# psvemmc-v10.net
KiCad netlist of a schematic drawn in EAGLE
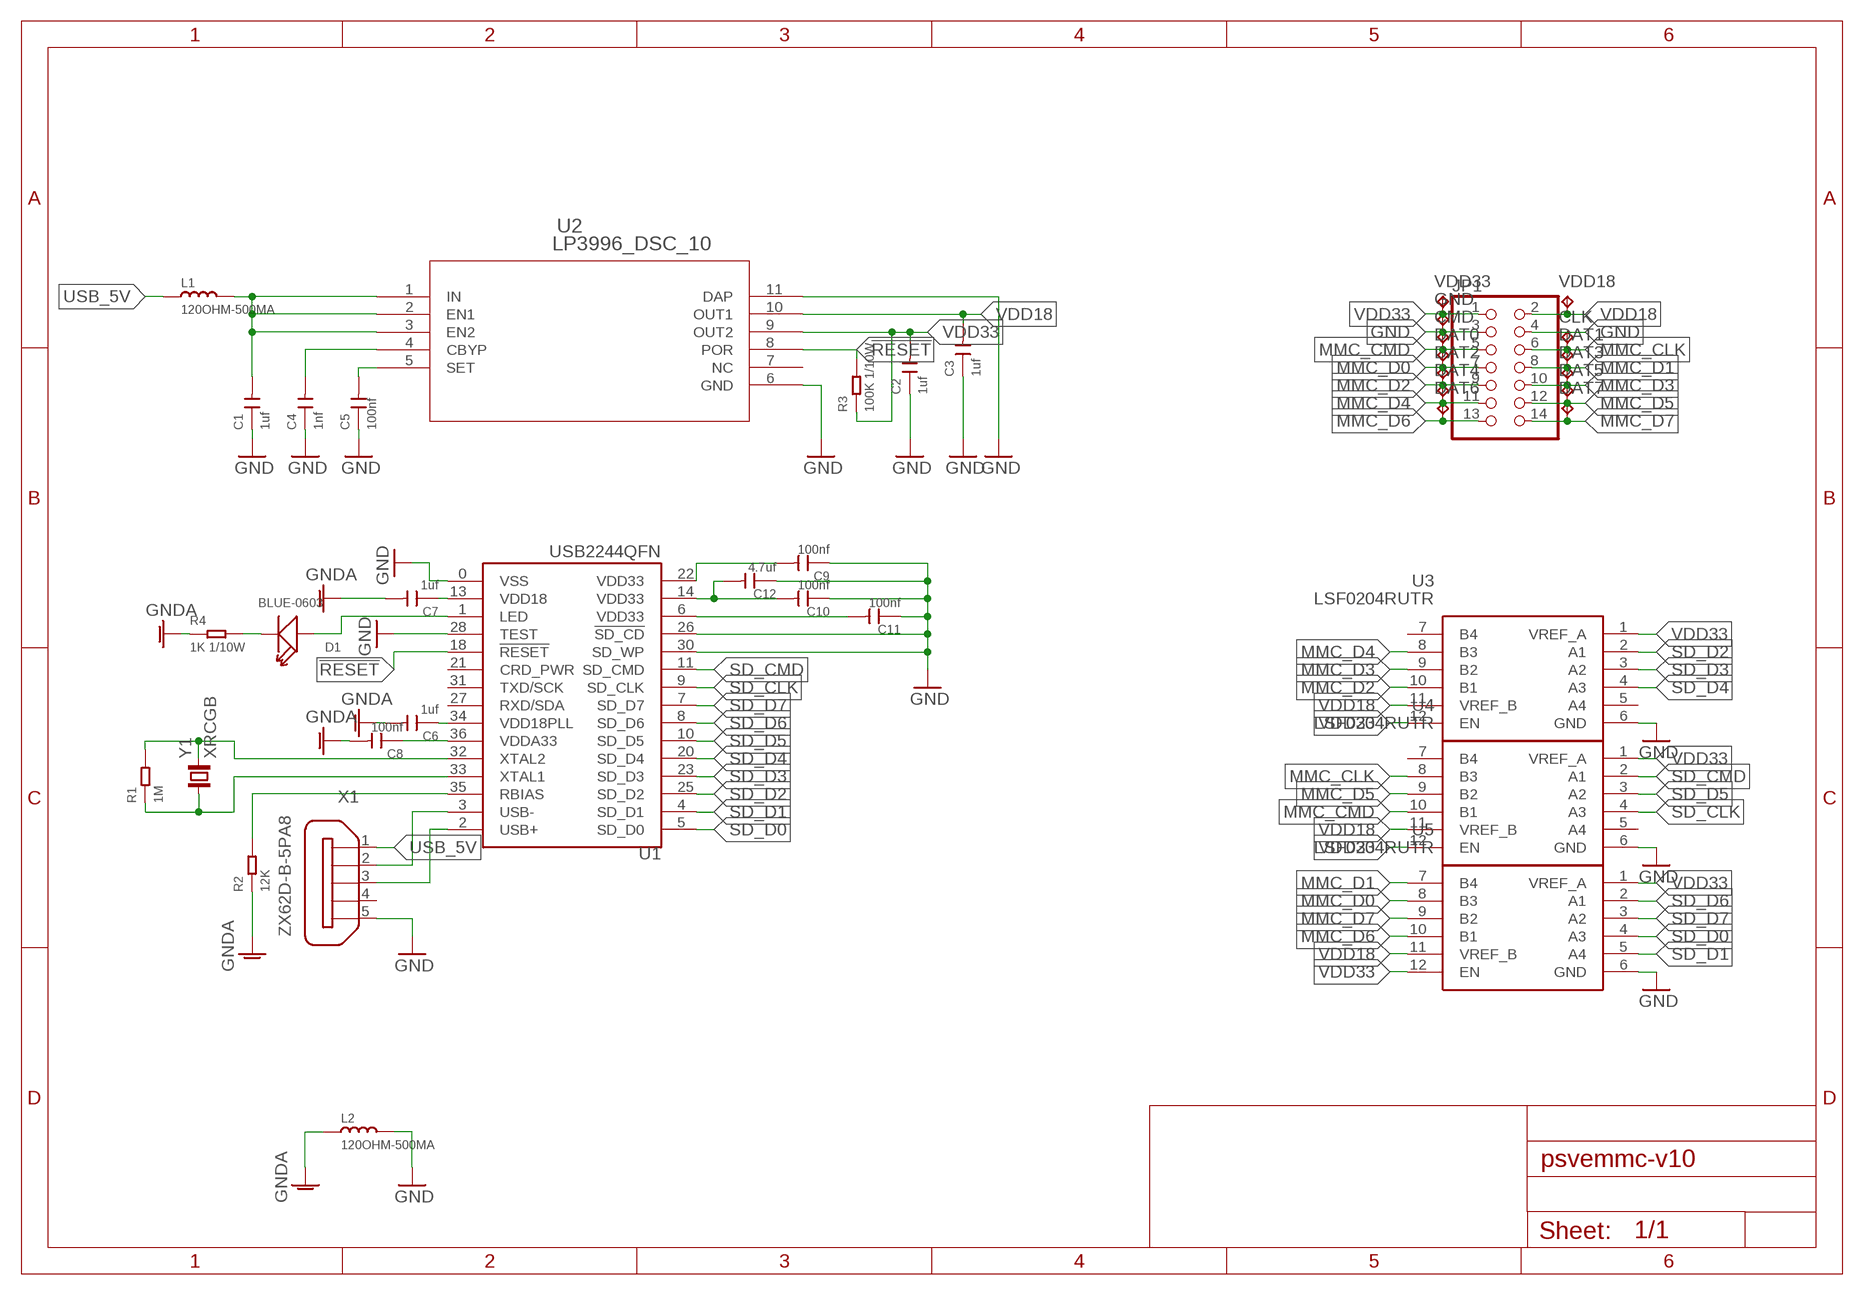
[diagram p0: schematic, sheet 1]

(export (version "E")
  (design (tool "Eeschema 10.0.6"))
  (components
    (comp (ref "C1")
      (value "1uf")
      (footprint "eagle-import:C0603")
      (fields (field (name "MPN") "CC0603KRX7R8BB105"))
      (libsource (lib "eagle-import") (part "CERAMIC-1UF-25V-10%-X7R(0603)"))
    )
    (comp (ref "C2")
      (value "1uf")
      (footprint "eagle-import:C0603")
      (fields (field (name "MPN") "CC0603KRX7R8BB105"))
      (libsource (lib "eagle-import") (part "CERAMIC-1UF-25V-10%-X7R(0603)"))
    )
    (comp (ref "C3")
      (value "1uf")
      (footprint "eagle-import:C0603")
      (fields (field (name "MPN") "CC0603KRX7R8BB105"))
      (libsource (lib "eagle-import") (part "CERAMIC-1UF-25V-10%-X7R(0603)"))
    )
    (comp (ref "C4")
      (value "1nf")
      (footprint "eagle-import:C0603")
      (fields (field (name "MPN") "GRM1885C1H102JA01D"))
      (libsource (lib "eagle-import") (part "CERAMIC-1NF-50V-5%-C0G(0603)"))
    )
    (comp (ref "C5")
      (value "100nf")
      (footprint "eagle-import:C0603")
      (fields (field (name "MPN") "CC0603KRX7R9BB104"))
      (libsource (lib "eagle-import") (part "CERAMIC-100NF-50V-10%-X7R(0603)"))
    )
    (comp (ref "C6")
      (value "1uf")
      (footprint "eagle-import:C0603")
      (fields (field (name "MPN") "CC0603KRX7R8BB105"))
      (libsource (lib "eagle-import") (part "CERAMIC-1UF-25V-10%-X7R(0603)"))
    )
    (comp (ref "C7")
      (value "1uf")
      (footprint "eagle-import:C0603")
      (fields (field (name "MPN") "CC0603KRX7R8BB105"))
      (libsource (lib "eagle-import") (part "CERAMIC-1UF-25V-10%-X7R(0603)"))
    )
    (comp (ref "C8")
      (value "100nf")
      (footprint "eagle-import:C0603")
      (fields (field (name "MPN") "CC0603KRX7R9BB104"))
      (libsource (lib "eagle-import") (part "CERAMIC-100NF-50V-10%-X7R(0603)"))
    )
    (comp (ref "C9")
      (value "100nf")
      (footprint "eagle-import:C0603")
      (fields (field (name "MPN") "CC0603KRX7R9BB104"))
      (libsource (lib "eagle-import") (part "CERAMIC-100NF-50V-10%-X7R(0603)"))
    )
    (comp (ref "C10")
      (value "100nf")
      (footprint "eagle-import:C0603")
      (fields (field (name "MPN") "CC0603KRX7R9BB104"))
      (libsource (lib "eagle-import") (part "CERAMIC-100NF-50V-10%-X7R(0603)"))
    )
    (comp (ref "C11")
      (value "100nf")
      (footprint "eagle-import:C0603")
      (fields (field (name "MPN") "CC0603KRX7R9BB104"))
      (libsource (lib "eagle-import") (part "CERAMIC-100NF-50V-10%-X7R(0603)"))
    )
    (comp (ref "C12")
      (value "4.7uf")
      (footprint "eagle-import:C0603")
      (fields (field (name "MPN") "CC0603KRX5R6BB475"))
      (libsource (lib "eagle-import") (part "CERAMIC-4.7UF-10V-10%-X5R(0603)"))
    )
    (comp (ref "CLK")
      (value "TPTP20SQ")
      (footprint "eagle-import:TP20SQ")
      (libsource (lib "eagle-import") (part "TPTP20SQ"))
    )
    (comp (ref "CMD")
      (value "TPTP20SQ")
      (footprint "eagle-import:TP20SQ")
      (libsource (lib "eagle-import") (part "TPTP20SQ"))
    )
    (comp (ref "D1")
      (value "BLUE-0603")
      (footprint "eagle-import:LED-0603")
      (fields (field (name "MPN") "19-217-BHC-ZL1M2RY-3T"))
      (libsource (lib "eagle-import") (part "SMD-LED-CLEAR-BLUE(0603)"))
    )
    (comp (ref "DAT0")
      (value "TPTP20SQ")
      (footprint "eagle-import:TP20SQ")
      (libsource (lib "eagle-import") (part "TPTP20SQ"))
    )
    (comp (ref "DAT1")
      (value "TPTP20SQ")
      (footprint "eagle-import:TP20SQ")
      (libsource (lib "eagle-import") (part "TPTP20SQ"))
    )
    (comp (ref "DAT2")
      (value "TPTP20SQ")
      (footprint "eagle-import:TP20SQ")
      (libsource (lib "eagle-import") (part "TPTP20SQ"))
    )
    (comp (ref "DAT3")
      (value "TPTP20SQ")
      (footprint "eagle-import:TP20SQ")
      (libsource (lib "eagle-import") (part "TPTP20SQ"))
    )
    (comp (ref "DAT4")
      (value "TPTP20SQ")
      (footprint "eagle-import:TP20SQ")
      (libsource (lib "eagle-import") (part "TPTP20SQ"))
    )
    (comp (ref "DAT5")
      (value "TPTP20SQ")
      (footprint "eagle-import:TP20SQ")
      (libsource (lib "eagle-import") (part "TPTP20SQ"))
    )
    (comp (ref "DAT6")
      (value "TPTP20SQ")
      (footprint "eagle-import:TP20SQ")
      (libsource (lib "eagle-import") (part "TPTP20SQ"))
    )
    (comp (ref "DAT7")
      (value "TPTP20SQ")
      (footprint "eagle-import:TP20SQ")
      (libsource (lib "eagle-import") (part "TPTP20SQ"))
    )
    (comp (ref "GND")
      (value "TPTP20SQ")
      (footprint "eagle-import:TP20SQ")
      (libsource (lib "eagle-import") (part "TPTP20SQ"))
    )
    (comp (ref "JP1")
      (value "PINHD-2X7")
      (footprint "eagle-import:2X07")
      (libsource (lib "eagle-import") (part "PINHD-2X7"))
    )
    (comp (ref "L1")
      (value "120OHM-500MA")
      (footprint "eagle-import:L0603")
      (fields (field (name "MPN") "BLM18AG121SN1D"))
      (libsource (lib "eagle-import") (part "SMD-FERRITE-CHIP-120-OHM-500MA(0603)"))
    )
    (comp (ref "L2")
      (value "120OHM-500MA")
      (footprint "eagle-import:L0603")
      (fields (field (name "MPN") "BLM18AG121SN1D"))
      (libsource (lib "eagle-import") (part "SMD-FERRITE-CHIP-120-OHM-500MA(0603)"))
    )
    (comp (ref "R1")
      (value "1M")
      (footprint "eagle-import:R0603")
      (fields (field (name "MPN") "RC0603FR-071ML"))
      (libsource (lib "eagle-import") (part "SMD-RES-1M-1%-1/10W(0603)"))
    )
    (comp (ref "R2")
      (value "12K")
      (footprint "eagle-import:R0603")
      (fields (field (name "MPN") "RC0603FR-0712KL"))
      (libsource (lib "eagle-import") (part "SMD-RES-12K-1%-1/10W(0603)"))
    )
    (comp (ref "R3")
      (value "100K 1/10W")
      (footprint "eagle-import:R0603")
      (fields (field (name "MPN") "RC0603JR-07100KL"))
      (libsource (lib "eagle-import") (part "SMD-RES-100K-5%-1/10W(0603)"))
    )
    (comp (ref "R4")
      (value "1K 1/10W")
      (footprint "eagle-import:R0603")
      (fields (field (name "MPN") "RC0603JR-071KL"))
      (libsource (lib "eagle-import") (part "SMD-RES-1K-5%-1/10W(0603)"))
    )
    (comp (ref "U1")
      (value "USB2244QFN")
      (footprint "eagle-import:QFN36")
      (libsource (lib "eagle-import") (part "USB2244QFN"))
    )
    (comp (ref "U2")
      (value "LP3996_DSC_10")
      (footprint "eagle-import:SDA10A")
      (fields (field (name "PARTNUMBER") "LP3996SD0833"))
      (libsource (lib "eagle-import") (part "LP3996_DSC_10"))
    )
    (comp (ref "U3")
      (value "LSF0204RUTR")
      (footprint "eagle-import:RUT(R-PUQFN-N12)")
      (libsource (lib "eagle-import") (part "LSF0204RUTR"))
    )
    (comp (ref "U4")
      (value "LSF0204RUTR")
      (footprint "eagle-import:RUT(R-PUQFN-N12)")
      (libsource (lib "eagle-import") (part "LSF0204RUTR"))
    )
    (comp (ref "U5")
      (value "LSF0204RUTR")
      (footprint "eagle-import:RUT(R-PUQFN-N12)")
      (libsource (lib "eagle-import") (part "LSF0204RUTR"))
    )
    (comp (ref "VDD18")
      (value "TPTP20SQ")
      (footprint "eagle-import:TP20SQ")
      (libsource (lib "eagle-import") (part "TPTP20SQ"))
    )
    (comp (ref "VDD33")
      (value "TPTP20SQ")
      (footprint "eagle-import:TP20SQ")
      (libsource (lib "eagle-import") (part "TPTP20SQ"))
    )
    (comp (ref "X1")
      (value "ZX62D-B-5PA8")
      (footprint "eagle-import:ZX62D-B-5PA8")
      (fields (field (name "MF") "Hirose"))
      (libsource (lib "eagle-import") (part "ZX62D-B-5PA8"))
    )
    (comp (ref "Y1")
      (value "XRCGB")
      (footprint "eagle-import:XRCGB")
      (libsource (lib "eagle-import") (part "XRCGB"))
    )
  )
  (nets
    (net (code "1") (name "/~{RESET}") (class "Default")
      (node (ref "R3") (pin "2") (pinfunction "2_2") (pintype "passive"))
      (node (ref "U1") (pin "18") (pinfunction "~{RESET}_18") (pintype "input"))
      (node (ref "U2") (pin "8") (pinfunction "POR_8") (pintype "passive"))
    )
    (net (code "2") (name "GND") (class "Default")
      (node (ref "C1") (pin "1") (pinfunction "1_1") (pintype "passive"))
      (node (ref "C10") (pin "1") (pinfunction "1_1") (pintype "passive"))
      (node (ref "C11") (pin "1") (pinfunction "1_1") (pintype "passive"))
      (node (ref "C12") (pin "1") (pinfunction "1_1") (pintype "passive"))
      (node (ref "C2") (pin "1") (pinfunction "1_1") (pintype "passive"))
      (node (ref "C3") (pin "1") (pinfunction "1_1") (pintype "passive"))
      (node (ref "C4") (pin "1") (pinfunction "1_1") (pintype "passive"))
      (node (ref "C5") (pin "1") (pinfunction "1_1") (pintype "passive"))
      (node (ref "C9") (pin "1") (pinfunction "1_1") (pintype "passive"))
      (node (ref "GND") (pin "TP") (pinfunction "TP_TP") (pintype "input"))
      (node (ref "JP1") (pin "3") (pinfunction "3_3") (pintype "passive"))
      (node (ref "JP1") (pin "4") (pinfunction "4_4") (pintype "passive"))
      (node (ref "L2") (pin "2") (pinfunction "2_2") (pintype "passive"))
      (node (ref "U1") (pin "0") (pinfunction "VSS_0") (pintype "bidirectional"))
      (node (ref "U1") (pin "26") (pinfunction "~{SD_CD}_26") (pintype "bidirectional"))
      (node (ref "U1") (pin "28") (pinfunction "TEST_28") (pintype "input"))
      (node (ref "U1") (pin "30") (pinfunction "SD_WP_30") (pintype "input"))
      (node (ref "U2") (pin "11") (pinfunction "DAP_11") (pintype "passive"))
      (node (ref "U2") (pin "6") (pinfunction "GND_6") (pintype "passive"))
      (node (ref "U3") (pin "6") (pinfunction "GND_6") (pintype "input"))
      (node (ref "U4") (pin "6") (pinfunction "GND_6") (pintype "input"))
      (node (ref "U5") (pin "6") (pinfunction "GND_6") (pintype "input"))
      (node (ref "X1") (pin "5") (pinfunction "5_5") (pintype "passive"))
    )
    (net (code "3") (name "GNDA") (class "Default")
      (node (ref "C6") (pin "2") (pinfunction "2_2") (pintype "passive"))
      (node (ref "C7") (pin "2") (pinfunction "2_2") (pintype "passive"))
      (node (ref "C8") (pin "2") (pinfunction "2_2") (pintype "passive"))
      (node (ref "L2") (pin "1") (pinfunction "1_1") (pintype "passive"))
      (node (ref "R2") (pin "1") (pinfunction "1_1") (pintype "passive"))
      (node (ref "R4") (pin "1") (pinfunction "1_1") (pintype "passive"))
    )
    (net (code "4") (name "MMC_CLK") (class "Default")
      (node (ref "CLK") (pin "TP") (pinfunction "TP_TP") (pintype "input"))
      (node (ref "JP1") (pin "6") (pinfunction "6_6") (pintype "passive"))
      (node (ref "U4") (pin "8") (pinfunction "B3_8") (pintype "input"))
    )
    (net (code "5") (name "MMC_CMD") (class "Default")
      (node (ref "CMD") (pin "TP") (pinfunction "TP_TP") (pintype "input"))
      (node (ref "JP1") (pin "5") (pinfunction "5_5") (pintype "passive"))
      (node (ref "U4") (pin "10") (pinfunction "B1_10") (pintype "input"))
    )
    (net (code "6") (name "MMC_D0") (class "Default")
      (node (ref "DAT0") (pin "TP") (pinfunction "TP_TP") (pintype "input"))
      (node (ref "JP1") (pin "7") (pinfunction "7_7") (pintype "passive"))
      (node (ref "U5") (pin "8") (pinfunction "B3_8") (pintype "input"))
    )
    (net (code "7") (name "MMC_D1") (class "Default")
      (node (ref "DAT1") (pin "TP") (pinfunction "TP_TP") (pintype "input"))
      (node (ref "JP1") (pin "8") (pinfunction "8_8") (pintype "passive"))
      (node (ref "U5") (pin "7") (pinfunction "B4_7") (pintype "input"))
    )
    (net (code "8") (name "MMC_D2") (class "Default")
      (node (ref "DAT2") (pin "TP") (pinfunction "TP_TP") (pintype "input"))
      (node (ref "JP1") (pin "9") (pinfunction "9_9") (pintype "passive"))
      (node (ref "U3") (pin "10") (pinfunction "B1_10") (pintype "input"))
    )
    (net (code "9") (name "MMC_D3") (class "Default")
      (node (ref "DAT3") (pin "TP") (pinfunction "TP_TP") (pintype "input"))
      (node (ref "JP1") (pin "10") (pinfunction "10_10") (pintype "passive"))
      (node (ref "U3") (pin "9") (pinfunction "B2_9") (pintype "input"))
    )
    (net (code "10") (name "MMC_D4") (class "Default")
      (node (ref "DAT4") (pin "TP") (pinfunction "TP_TP") (pintype "input"))
      (node (ref "JP1") (pin "11") (pinfunction "11_11") (pintype "passive"))
      (node (ref "U3") (pin "8") (pinfunction "B3_8") (pintype "input"))
    )
    (net (code "11") (name "MMC_D5") (class "Default")
      (node (ref "DAT5") (pin "TP") (pinfunction "TP_TP") (pintype "input"))
      (node (ref "JP1") (pin "12") (pinfunction "12_12") (pintype "passive"))
      (node (ref "U4") (pin "9") (pinfunction "B2_9") (pintype "input"))
    )
    (net (code "12") (name "MMC_D6") (class "Default")
      (node (ref "DAT6") (pin "TP") (pinfunction "TP_TP") (pintype "input"))
      (node (ref "JP1") (pin "13") (pinfunction "13_13") (pintype "passive"))
      (node (ref "U5") (pin "10") (pinfunction "B1_10") (pintype "input"))
    )
    (net (code "13") (name "MMC_D7") (class "Default")
      (node (ref "DAT7") (pin "TP") (pinfunction "TP_TP") (pintype "input"))
      (node (ref "JP1") (pin "14") (pinfunction "14_14") (pintype "passive"))
      (node (ref "U5") (pin "9") (pinfunction "B2_9") (pintype "input"))
    )
    (net (code "14") (name "Net-(D1-Pad-)") (class "Default")
      (node (ref "D1") (pin "-") (pinfunction "-_-") (pintype "passive"))
      (node (ref "R4") (pin "2") (pinfunction "2_2") (pintype "passive"))
    )
    (net (code "15") (name "Net-(U1-LED)") (class "Default")
      (node (ref "D1") (pin "+") (pinfunction "+_+") (pintype "passive"))
      (node (ref "U1") (pin "1") (pinfunction "LED_1") (pintype "bidirectional"))
    )
    (net (code "16") (name "Net-(U1-RBIAS)") (class "Default")
      (node (ref "R2") (pin "2") (pinfunction "2_2") (pintype "passive"))
      (node (ref "U1") (pin "35") (pinfunction "RBIAS_35") (pintype "bidirectional"))
    )
    (net (code "17") (name "Net-(U1-USB+)") (class "Default")
      (node (ref "U1") (pin "2") (pinfunction "USB+_2") (pintype "bidirectional"))
      (node (ref "X1") (pin "3") (pinfunction "3_3") (pintype "passive"))
    )
    (net (code "18") (name "Net-(U1-USB-)") (class "Default")
      (node (ref "U1") (pin "3") (pinfunction "USB-_3") (pintype "bidirectional"))
      (node (ref "X1") (pin "2") (pinfunction "2_2") (pintype "passive"))
    )
    (net (code "19") (name "Net-(U1-VDD18)") (class "Default")
      (node (ref "C7") (pin "1") (pinfunction "1_1") (pintype "passive"))
      (node (ref "U1") (pin "13") (pinfunction "VDD18_13") (pintype "bidirectional"))
    )
    (net (code "20") (name "Net-(U1-VDD18PLL)") (class "Default")
      (node (ref "C6") (pin "1") (pinfunction "1_1") (pintype "passive"))
      (node (ref "U1") (pin "34") (pinfunction "VDD18PLL_34") (pintype "bidirectional"))
    )
    (net (code "21") (name "Net-(U1-XTAL1)") (class "Default")
      (node (ref "R1") (pin "1") (pinfunction "1_1") (pintype "passive"))
      (node (ref "U1") (pin "33") (pinfunction "XTAL1_33") (pintype "input"))
      (node (ref "Y1") (pin "1") (pinfunction "1_1") (pintype "passive"))
    )
    (net (code "22") (name "Net-(U1-XTAL2)") (class "Default")
      (node (ref "R1") (pin "2") (pinfunction "2_2") (pintype "passive"))
      (node (ref "U1") (pin "32") (pinfunction "XTAL2_32") (pintype "output"))
      (node (ref "Y1") (pin "3") (pinfunction "2_3") (pintype "passive"))
    )
    (net (code "23") (name "Net-(U2-CBYP)") (class "Default")
      (node (ref "C4") (pin "2") (pinfunction "2_2") (pintype "passive"))
      (node (ref "U2") (pin "4") (pinfunction "CBYP_4") (pintype "passive"))
    )
    (net (code "24") (name "Net-(U2-EN1)") (class "Default")
      (node (ref "C1") (pin "2") (pinfunction "2_2") (pintype "passive"))
      (node (ref "L1") (pin "2") (pinfunction "2_2") (pintype "passive"))
      (node (ref "U2") (pin "1") (pinfunction "IN_1") (pintype "input"))
      (node (ref "U2") (pin "2") (pinfunction "EN1_2") (pintype "passive"))
      (node (ref "U2") (pin "3") (pinfunction "EN2_3") (pintype "passive"))
    )
    (net (code "25") (name "Net-(U2-SET)") (class "Default")
      (node (ref "C5") (pin "2") (pinfunction "2_2") (pintype "passive"))
      (node (ref "U2") (pin "5") (pinfunction "SET_5") (pintype "passive"))
    )
    (net (code "26") (name "SD_CLK") (class "Default")
      (node (ref "U1") (pin "9") (pinfunction "SD_CLK_9") (pintype "output"))
      (node (ref "U4") (pin "4") (pinfunction "A3_4") (pintype "input"))
    )
    (net (code "27") (name "SD_CMD") (class "Default")
      (node (ref "U1") (pin "11") (pinfunction "SD_CMD_11") (pintype "bidirectional"))
      (node (ref "U4") (pin "2") (pinfunction "A1_2") (pintype "input"))
    )
    (net (code "28") (name "SD_D0") (class "Default")
      (node (ref "U1") (pin "5") (pinfunction "SD_D0_5") (pintype "bidirectional"))
      (node (ref "U5") (pin "4") (pinfunction "A3_4") (pintype "input"))
    )
    (net (code "29") (name "SD_D1") (class "Default")
      (node (ref "U1") (pin "4") (pinfunction "SD_D1_4") (pintype "bidirectional"))
      (node (ref "U5") (pin "5") (pinfunction "A4_5") (pintype "input"))
    )
    (net (code "30") (name "SD_D2") (class "Default")
      (node (ref "U1") (pin "25") (pinfunction "SD_D2_25") (pintype "bidirectional"))
      (node (ref "U3") (pin "2") (pinfunction "A1_2") (pintype "input"))
    )
    (net (code "31") (name "SD_D3") (class "Default")
      (node (ref "U1") (pin "23") (pinfunction "SD_D3_23") (pintype "bidirectional"))
      (node (ref "U3") (pin "3") (pinfunction "A2_3") (pintype "input"))
    )
    (net (code "32") (name "SD_D4") (class "Default")
      (node (ref "U1") (pin "20") (pinfunction "SD_D4_20") (pintype "bidirectional"))
      (node (ref "U3") (pin "4") (pinfunction "A3_4") (pintype "input"))
    )
    (net (code "33") (name "SD_D5") (class "Default")
      (node (ref "U1") (pin "10") (pinfunction "SD_D5_10") (pintype "bidirectional"))
      (node (ref "U4") (pin "3") (pinfunction "A2_3") (pintype "input"))
    )
    (net (code "34") (name "SD_D6") (class "Default")
      (node (ref "U1") (pin "8") (pinfunction "SD_D6_8") (pintype "bidirectional"))
      (node (ref "U5") (pin "2") (pinfunction "A1_2") (pintype "input"))
    )
    (net (code "35") (name "SD_D7") (class "Default")
      (node (ref "U1") (pin "7") (pinfunction "SD_D7_7") (pintype "bidirectional"))
      (node (ref "U5") (pin "3") (pinfunction "A2_3") (pintype "input"))
    )
    (net (code "36") (name "USB_5V") (class "Default")
      (node (ref "L1") (pin "1") (pinfunction "1_1") (pintype "passive"))
      (node (ref "X1") (pin "1") (pinfunction "1_1") (pintype "passive"))
    )
    (net (code "37") (name "VDD18") (class "Default")
      (node (ref "C3") (pin "2") (pinfunction "2_2") (pintype "passive"))
      (node (ref "JP1") (pin "2") (pinfunction "2_2") (pintype "passive"))
      (node (ref "U2") (pin "10") (pinfunction "OUT1_10") (pintype "output"))
      (node (ref "U3") (pin "11") (pinfunction "VREF_B_11") (pintype "input"))
      (node (ref "U4") (pin "11") (pinfunction "VREF_B_11") (pintype "input"))
      (node (ref "U5") (pin "11") (pinfunction "VREF_B_11") (pintype "input"))
      (node (ref "VDD18") (pin "TP") (pinfunction "TP_TP") (pintype "input"))
    )
    (net (code "38") (name "VDD33") (class "Default")
      (node (ref "C10") (pin "2") (pinfunction "2_2") (pintype "passive"))
      (node (ref "C11") (pin "2") (pinfunction "2_2") (pintype "passive"))
      (node (ref "C12") (pin "2") (pinfunction "2_2") (pintype "passive"))
      (node (ref "C2") (pin "2") (pinfunction "2_2") (pintype "passive"))
      (node (ref "C8") (pin "1") (pinfunction "1_1") (pintype "passive"))
      (node (ref "C9") (pin "2") (pinfunction "2_2") (pintype "passive"))
      (node (ref "JP1") (pin "1") (pinfunction "1_1") (pintype "passive"))
      (node (ref "R3") (pin "1") (pinfunction "1_1") (pintype "passive"))
      (node (ref "U1") (pin "14") (pinfunction "VDD33_14") (pintype "bidirectional"))
      (node (ref "U1") (pin "22") (pinfunction "VDD33_22") (pintype "bidirectional"))
      (node (ref "U1") (pin "36") (pinfunction "VDDA33_36") (pintype "bidirectional"))
      (node (ref "U1") (pin "6") (pinfunction "VDD33_6") (pintype "bidirectional"))
      (node (ref "U2") (pin "9") (pinfunction "OUT2_9") (pintype "output"))
      (node (ref "U3") (pin "1") (pinfunction "VREF_A_1") (pintype "input"))
      (node (ref "U3") (pin "12") (pinfunction "EN_12") (pintype "input"))
      (node (ref "U4") (pin "1") (pinfunction "VREF_A_1") (pintype "input"))
      (node (ref "U4") (pin "12") (pinfunction "EN_12") (pintype "input"))
      (node (ref "U5") (pin "1") (pinfunction "VREF_A_1") (pintype "input"))
      (node (ref "U5") (pin "12") (pinfunction "EN_12") (pintype "input"))
      (node (ref "VDD33") (pin "TP") (pinfunction "TP_TP") (pintype "input"))
    )
    (net (code "39") (name "unconnected-(U1-CRD_PWR-Pad21)") (class "Default")
      (node (ref "U1") (pin "21") (pinfunction "CRD_PWR_21") (pintype "bidirectional"))
    )
    (net (code "40") (name "unconnected-(U1-RXD{slash}SDA-Pad27)") (class "Default")
      (node (ref "U1") (pin "27") (pinfunction "RXD/SDA_27") (pintype "bidirectional"))
    )
    (net (code "41") (name "unconnected-(U1-TXD{slash}SCK-Pad31)") (class "Default")
      (node (ref "U1") (pin "31") (pinfunction "TXD/SCK_31") (pintype "bidirectional"))
    )
    (net (code "42") (name "unconnected-(U2-NC-Pad7)") (class "Default")
      (node (ref "U2") (pin "7") (pinfunction "NC_7") (pintype "passive"))
    )
    (net (code "43") (name "unconnected-(U3-A4-Pad5)") (class "Default")
      (node (ref "U3") (pin "5") (pinfunction "A4_5") (pintype "input"))
    )
    (net (code "44") (name "unconnected-(U3-B4-Pad7)") (class "Default")
      (node (ref "U3") (pin "7") (pinfunction "B4_7") (pintype "input"))
    )
    (net (code "45") (name "unconnected-(U4-A4-Pad5)") (class "Default")
      (node (ref "U4") (pin "5") (pinfunction "A4_5") (pintype "input"))
    )
    (net (code "46") (name "unconnected-(U4-B4-Pad7)") (class "Default")
      (node (ref "U4") (pin "7") (pinfunction "B4_7") (pintype "input"))
    )
    (net (code "47") (name "unconnected-(X1-Pad4)") (class "Default")
      (node (ref "X1") (pin "4") (pinfunction "4_4") (pintype "passive"))
    )
  )
)
